# LDO_All.net
KiCad netlist of a schematic drawn in Altium Designer
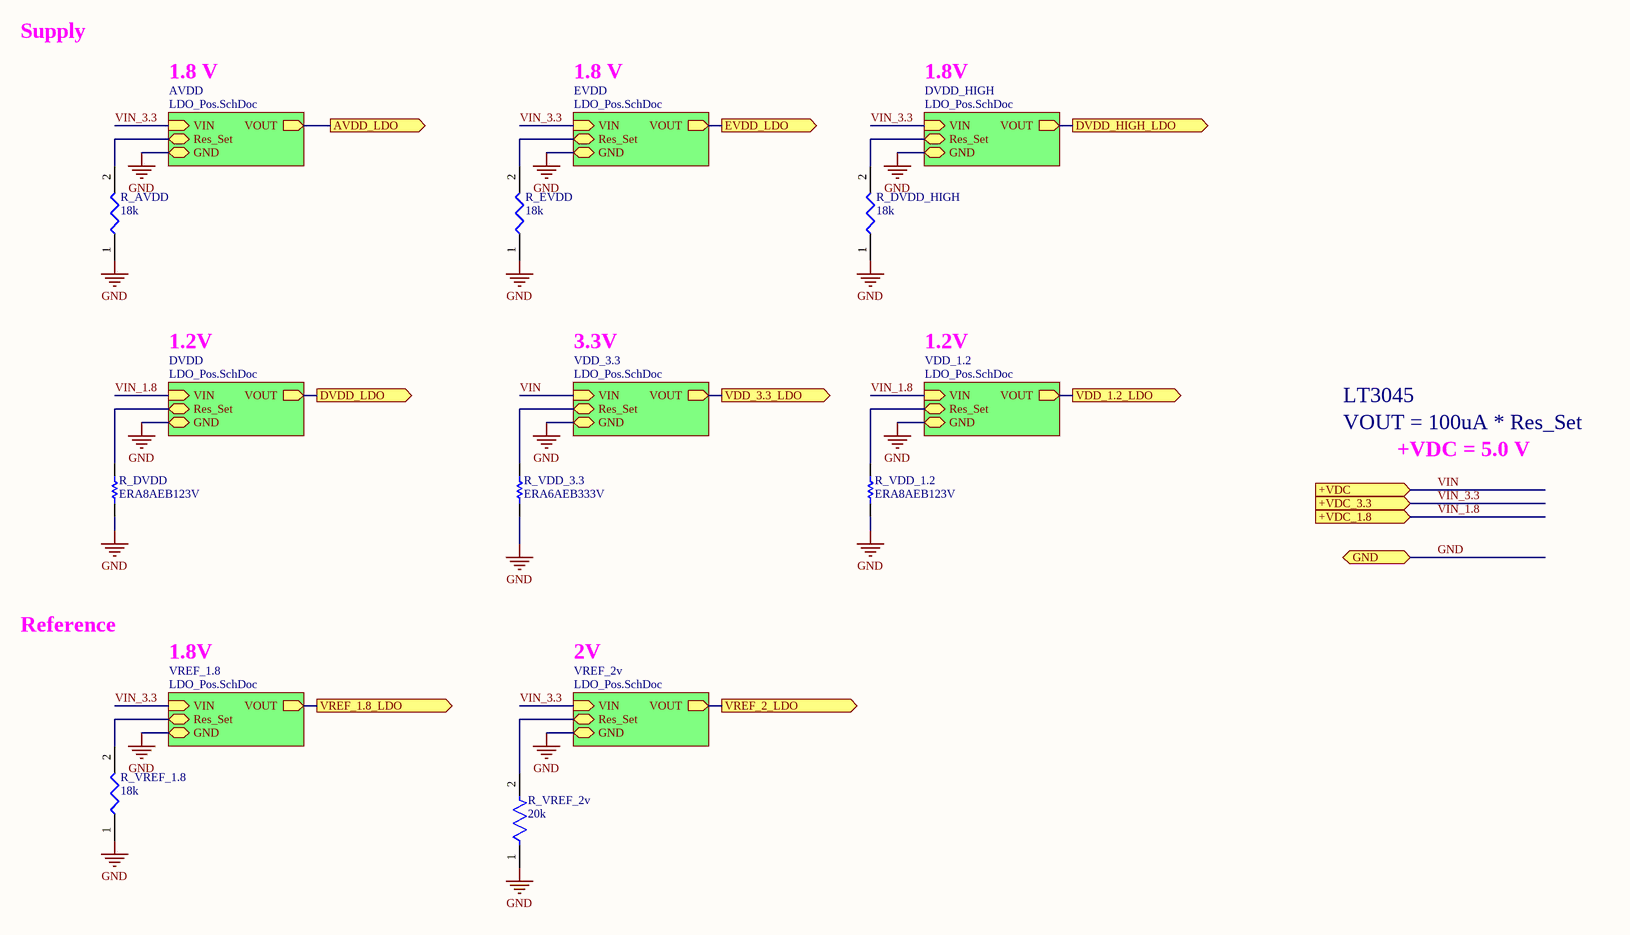
[diagram p0: LDO_All.SchDoc]

(export (version "E")
  (design (tool "Eeschema 10.0.6"))
  (components
    (comp (ref "R_AVDD")
      (value "18k")
      (footprint "MRI_ADC:ERA3KV_(0603)")
      (description "Resistor")
      (fields (field (name "MANUFACTURER_PART_NUMBER") "ERA-3VRW1802V"))
      (libsource (lib "MRI_ADC") (part "Res 18k 0.05% 0603"))
    )
    (comp (ref "R_DVDD")
      (value "ERA8AEB123V")
      (footprint "RESC3216X70X50NL20T25")
      (fields (field (name "MANUFACTURER") "Panasonic"))
      (libsource (lib "Altium Content Vault") (part "RES"))
    )
    (comp (ref "R_DVDD_HIGH")
      (value "18k")
      (footprint "MRI_ADC:ERA3KV_(0603)")
      (description "Resistor")
      (fields (field (name "MANUFACTURER_PART_NUMBER") "ERA-3VRW1802V"))
      (libsource (lib "MRI_ADC") (part "Res 18k 0.05% 0603"))
    )
    (comp (ref "R_EVDD")
      (value "18k")
      (footprint "MRI_ADC:ERA3KV_(0603)")
      (description "Resistor")
      (fields (field (name "MANUFACTURER_PART_NUMBER") "ERA-3VRW1802V"))
      (libsource (lib "MRI_ADC") (part "Res 18k 0.05% 0603"))
    )
    (comp (ref "R_VDD_1.2")
      (value "ERA8AEB123V")
      (footprint "RESC3216X70X50NL20T25")
      (fields (field (name "MANUFACTURER") "Panasonic"))
      (libsource (lib "Altium Content Vault") (part "RES"))
    )
    (comp (ref "R_VDD_3.3")
      (value "ERA6AEB333V")
      (footprint "RESC2013X60X40NL20T25")
      (fields (field (name "MANUFACTURER") "Panasonic"))
      (libsource (lib "Altium Content Vault") (part "RES"))
    )
    (comp (ref "R_VREF_1.8")
      (value "18k")
      (footprint "MRI_ADC:ERA3KV_(0603)")
      (description "Resistor")
      (fields (field (name "MANUFACTURER_PART_NUMBER") "ERA-3VRW1802V"))
      (libsource (lib "MRI_ADC") (part "Res 18k 0.05% 0603"))
    )
    (comp (ref "R_VREF_2v")
      (value "20k")
      (footprint "FP-RT0603-MFG")
      (description "RES SMD 20K OHM 0.1% 1/10W 0603")
      (fields
        (field (name "MANUFACTURER") "Yageo")
        (field (name "MANUFACTURER PART NUMBER") "RT0603BRE0720KL")
      )
      (libsource (lib "Altium Content Vault") (part "1029c3af85768c4190bb7ad29bc67b5"))
    )
  )
  (nets
    (net (code "5") (name "/Res_Set") (class "Default")
      (node (ref "R_VREF_1.8") (pin "2") (pinfunction "2_2") (pintype "passive"))
    )
    (net (code "6") (name "/Res_Set_1") (class "Default")
      (node (ref "R_AVDD") (pin "2") (pinfunction "2_2") (pintype "passive"))
    )
    (net (code "7") (name "/Res_Set_2") (class "Default")
      (node (ref "R_VDD_3.3") (pin "2") (pinfunction "2_2") (pintype "passive"))
    )
    (net (code "8") (name "/Res_Set_3") (class "Default")
      (node (ref "R_EVDD") (pin "2") (pinfunction "2_2") (pintype "passive"))
    )
    (net (code "9") (name "/Res_Set_4") (class "Default")
      (node (ref "R_DVDD") (pin "2") (pinfunction "2_2") (pintype "passive"))
    )
    (net (code "10") (name "/Res_Set_5") (class "Default")
      (node (ref "R_VREF_2v") (pin "2") (pinfunction "2_2") (pintype "passive"))
    )
    (net (code "11") (name "/Res_Set_6") (class "Default")
      (node (ref "R_DVDD_HIGH") (pin "2") (pinfunction "2_2") (pintype "passive"))
    )
    (net (code "12") (name "/Res_Set_7") (class "Default")
      (node (ref "R_VDD_1.2") (pin "2") (pinfunction "2_2") (pintype "passive"))
    )
    (net (code "20") (name "GND") (class "Default")
      (node (ref "R_AVDD") (pin "1") (pinfunction "1_1") (pintype "passive"))
      (node (ref "R_DVDD") (pin "1") (pinfunction "1_1") (pintype "passive"))
      (node (ref "R_DVDD_HIGH") (pin "1") (pinfunction "1_1") (pintype "passive"))
      (node (ref "R_EVDD") (pin "1") (pinfunction "1_1") (pintype "passive"))
      (node (ref "R_VDD_1.2") (pin "1") (pinfunction "1_1") (pintype "passive"))
      (node (ref "R_VDD_3.3") (pin "1") (pinfunction "1_1") (pintype "passive"))
      (node (ref "R_VREF_1.8") (pin "1") (pinfunction "1_1") (pintype "passive"))
      (node (ref "R_VREF_2v") (pin "1") (pinfunction "1_1") (pintype "passive"))
    )
  )
)
